# 06_-_External_ADC.net
KiCad netlist of a schematic drawn in Altium Designer
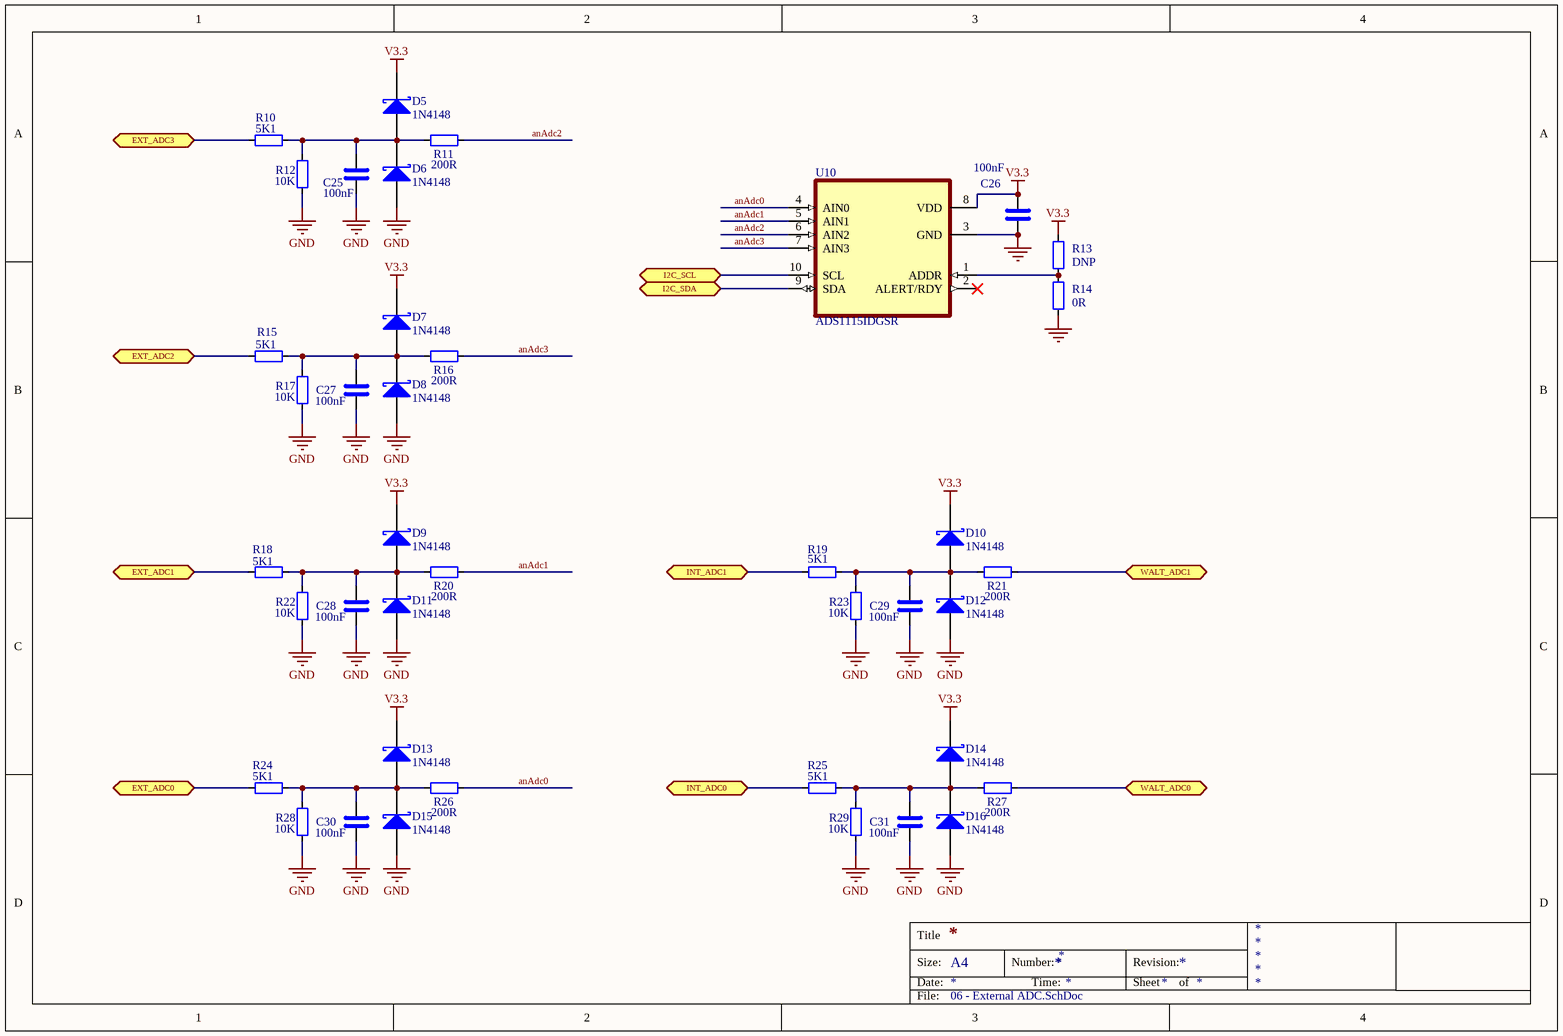
[diagram p0: 06 - External ADC.SchDoc]

(export (version "E")
  (design (tool "Eeschema 10.0.6"))
  (components
    (comp (ref "C25")
      (value "100nF")
      (footprint "CAP_0603")
      (fields (field (name "LCSC PART") "C6119867"))
      (libsource (lib "WalterFeels") (part "C"))
    )
    (comp (ref "C26")
      (value "100nF")
      (footprint "CAP_0603")
      (fields (field (name "LCSC PART") "C6119867"))
      (libsource (lib "WalterFeels") (part "C"))
    )
    (comp (ref "C27")
      (value "100nF")
      (footprint "CAP_0603")
      (fields (field (name "LCSC PART") "C6119867"))
      (libsource (lib "WalterFeels") (part "C"))
    )
    (comp (ref "C28")
      (value "100nF")
      (footprint "CAP_0603")
      (fields (field (name "LCSC PART") "C6119867"))
      (libsource (lib "WalterFeels") (part "C"))
    )
    (comp (ref "C29")
      (value "100nF")
      (footprint "CAP_0603")
      (fields (field (name "LCSC PART") "C6119867"))
      (libsource (lib "WalterFeels") (part "C"))
    )
    (comp (ref "C30")
      (value "100nF")
      (footprint "CAP_0603")
      (fields (field (name "LCSC PART") "C6119867"))
      (libsource (lib "WalterFeels") (part "C"))
    )
    (comp (ref "C31")
      (value "100nF")
      (footprint "CAP_0603")
      (fields (field (name "LCSC PART") "C6119867"))
      (libsource (lib "WalterFeels") (part "C"))
    )
    (comp (ref "D5")
      (value "1N4148")
      (footprint "SOD323_STM_NW")
      (description "1N4148_KA")
      (fields (field (name "LCSC PART") "C84063"))
      (libsource (lib "ahmet") (part "1N4148_KA"))
    )
    (comp (ref "D6")
      (value "1N4148")
      (footprint "SOD323_STM_NW")
      (description "1N4148_KA")
      (fields (field (name "LCSC PART") "C84063"))
      (libsource (lib "ahmet") (part "1N4148_KA"))
    )
    (comp (ref "D7")
      (value "1N4148")
      (footprint "SOD323_STM_NW")
      (description "1N4148_KA")
      (fields (field (name "LCSC PART") "C84063"))
      (libsource (lib "ahmet") (part "1N4148_KA"))
    )
    (comp (ref "D8")
      (value "1N4148")
      (footprint "SOD323_STM_NW")
      (description "1N4148_KA")
      (fields (field (name "LCSC PART") "C84063"))
      (libsource (lib "ahmet") (part "1N4148_KA"))
    )
    (comp (ref "D9")
      (value "1N4148")
      (footprint "SOD323_STM_NW")
      (description "1N4148_KA")
      (fields (field (name "LCSC PART") "C84063"))
      (libsource (lib "ahmet") (part "1N4148_KA"))
    )
    (comp (ref "D10")
      (value "1N4148")
      (footprint "SOD323_STM_NW")
      (description "1N4148_KA")
      (fields (field (name "LCSC PART") "C84063"))
      (libsource (lib "ahmet") (part "1N4148_KA"))
    )
    (comp (ref "D11")
      (value "1N4148")
      (footprint "SOD323_STM_NW")
      (description "1N4148_KA")
      (fields (field (name "LCSC PART") "C84063"))
      (libsource (lib "ahmet") (part "1N4148_KA"))
    )
    (comp (ref "D12")
      (value "1N4148")
      (footprint "SOD323_STM_NW")
      (description "1N4148_KA")
      (fields (field (name "LCSC PART") "C84063"))
      (libsource (lib "ahmet") (part "1N4148_KA"))
    )
    (comp (ref "D13")
      (value "1N4148")
      (footprint "SOD323_STM_NW")
      (description "1N4148_KA")
      (fields (field (name "LCSC PART") "C84063"))
      (libsource (lib "ahmet") (part "1N4148_KA"))
    )
    (comp (ref "D14")
      (value "1N4148")
      (footprint "SOD323_STM_NW")
      (description "1N4148_KA")
      (fields (field (name "LCSC PART") "C84063"))
      (libsource (lib "ahmet") (part "1N4148_KA"))
    )
    (comp (ref "D15")
      (value "1N4148")
      (footprint "SOD323_STM_NW")
      (description "1N4148_KA")
      (fields (field (name "LCSC PART") "C84063"))
      (libsource (lib "ahmet") (part "1N4148_KA"))
    )
    (comp (ref "D16")
      (value "1N4148")
      (footprint "SOD323_STM_NW")
      (description "1N4148_KA")
      (fields (field (name "LCSC PART") "C84063"))
      (libsource (lib "ahmet") (part "1N4148_KA"))
    )
    (comp (ref "R10")
      (value "5K1")
      (footprint "RES_0603")
      (fields (field (name "LCSC PART") "C23186") (field (name "Comment") "5K1 1%"))
      (libsource (lib "Device") (part "R"))
    )
    (comp (ref "R11")
      (value "200R")
      (footprint "RES_0603")
      (fields (field (name "LCSC PART") "C2907123") (field (name "Comment") "200R %5"))
      (libsource (lib "Device") (part "R"))
    )
    (comp (ref "R12")
      (value "10K")
      (footprint "RES_0603")
      (fields (field (name "LCSC PART") "C25804") (field (name "Comment") "10K 1%"))
      (libsource (lib "") (part "R_1"))
    )
    (comp (ref "R13") (value "DNP") (footprint "RES_0603") (libsource (lib "") (part "R_2")))
    (comp (ref "R14")
      (value "0R")
      (footprint "RES_0603")
      (fields (field (name "LCSC PART") "C15402"))
      (libsource (lib "") (part "R_2"))
    )
    (comp (ref "R15")
      (value "5K1")
      (footprint "RES_0603")
      (fields (field (name "LCSC PART") "C23186") (field (name "Comment") "5K1 1%"))
      (libsource (lib "Device") (part "R"))
    )
    (comp (ref "R16")
      (value "200R")
      (footprint "RES_0603")
      (fields (field (name "LCSC PART") "C2907123") (field (name "Comment") "200R %5"))
      (libsource (lib "Device") (part "R"))
    )
    (comp (ref "R17")
      (value "10K")
      (footprint "RES_0603")
      (fields (field (name "LCSC PART") "C25804") (field (name "Comment") "10K 1%"))
      (libsource (lib "") (part "R_1"))
    )
    (comp (ref "R18")
      (value "5K1")
      (footprint "RES_0603")
      (fields (field (name "LCSC PART") "C23186") (field (name "Comment") "5K1 1%"))
      (libsource (lib "Device") (part "R"))
    )
    (comp (ref "R19")
      (value "5K1")
      (footprint "RES_0603")
      (fields (field (name "LCSC PART") "C23186") (field (name "Comment") "5K1 1%"))
      (libsource (lib "Device") (part "R"))
    )
    (comp (ref "R20")
      (value "200R")
      (footprint "RES_0603")
      (fields (field (name "LCSC PART") "C2907123") (field (name "Comment") "200R %5"))
      (libsource (lib "Device") (part "R"))
    )
    (comp (ref "R21")
      (value "200R")
      (footprint "RES_0603")
      (fields (field (name "LCSC PART") "C2907123") (field (name "Comment") "200R %5"))
      (libsource (lib "Device") (part "R"))
    )
    (comp (ref "R22")
      (value "10K")
      (footprint "RES_0603")
      (fields (field (name "LCSC PART") "C25804") (field (name "Comment") "10K 1%"))
      (libsource (lib "") (part "R_1"))
    )
    (comp (ref "R23")
      (value "10K")
      (footprint "RES_0603")
      (fields (field (name "LCSC PART") "C25804") (field (name "Comment") "10K 1%"))
      (libsource (lib "") (part "R_1"))
    )
    (comp (ref "R24")
      (value "5K1")
      (footprint "RES_0603")
      (fields (field (name "LCSC PART") "C23186") (field (name "Comment") "5K1 1%"))
      (libsource (lib "Device") (part "R"))
    )
    (comp (ref "R25")
      (value "5K1")
      (footprint "RES_0603")
      (fields (field (name "LCSC PART") "C23186") (field (name "Comment") "5K1 1%"))
      (libsource (lib "Device") (part "R"))
    )
    (comp (ref "R26")
      (value "200R")
      (footprint "RES_0603")
      (fields (field (name "LCSC PART") "C2907123") (field (name "Comment") "200R %5"))
      (libsource (lib "Device") (part "R"))
    )
    (comp (ref "R27")
      (value "200R")
      (footprint "RES_0603")
      (fields (field (name "LCSC PART") "C2907123") (field (name "Comment") "200R %5"))
      (libsource (lib "Device") (part "R"))
    )
    (comp (ref "R28")
      (value "10K")
      (footprint "RES_0603")
      (fields (field (name "LCSC PART") "C25804") (field (name "Comment") "10K 1%"))
      (libsource (lib "") (part "R_1"))
    )
    (comp (ref "R29")
      (value "10K")
      (footprint "RES_0603")
      (fields (field (name "LCSC PART") "C25804") (field (name "Comment") "10K 1%"))
      (libsource (lib "") (part "R_1"))
    )
    (comp (ref "U10")
      (value "ADS1115IDGSR")
      (footprint "SOP50P490X110-10N")
      (fields (field (name "LCSC PART") "C37593"))
      (libsource (lib "ahmet") (part "ADS1015IDGSR"))
    )
  )
  (nets
    (net (code "1") (name "/EXT_ADC0") (class "Default")
      (node (ref "R24") (pin "1") (pinfunction "1_1") (pintype "passive"))
    )
    (net (code "2") (name "/EXT_ADC1") (class "Default")
      (node (ref "R18") (pin "1") (pinfunction "1_1") (pintype "passive"))
    )
    (net (code "3") (name "/EXT_ADC2") (class "Default")
      (node (ref "R15") (pin "1") (pinfunction "1_1") (pintype "passive"))
    )
    (net (code "4") (name "/EXT_ADC3") (class "Default")
      (node (ref "R10") (pin "1") (pinfunction "1_1") (pintype "passive"))
    )
    (net (code "5") (name "/I2C_SCL") (class "Default")
      (node (ref "U10") (pin "10") (pinfunction "SCL_10") (pintype "input"))
    )
    (net (code "6") (name "/I2C_SDA") (class "Default")
      (node (ref "U10") (pin "9") (pinfunction "SDA_9") (pintype "bidirectional"))
    )
    (net (code "7") (name "/INT_ADC0") (class "Default")
      (node (ref "R25") (pin "1") (pinfunction "1_1") (pintype "passive"))
    )
    (net (code "8") (name "/INT_ADC1") (class "Default")
      (node (ref "R19") (pin "1") (pinfunction "1_1") (pintype "passive"))
    )
    (net (code "9") (name "/WALT_ADC0") (class "Default")
      (node (ref "R27") (pin "2") (pinfunction "2_2") (pintype "passive"))
    )
    (net (code "10") (name "/WALT_ADC1") (class "Default")
      (node (ref "R21") (pin "2") (pinfunction "2_2") (pintype "passive"))
    )
    (net (code "11") (name "/anAdc0") (class "Default")
      (node (ref "R26") (pin "2") (pinfunction "2_2") (pintype "passive"))
      (node (ref "U10") (pin "4") (pinfunction "AIN0_4") (pintype "input"))
    )
    (net (code "12") (name "/anAdc1") (class "Default")
      (node (ref "R20") (pin "2") (pinfunction "2_2") (pintype "passive"))
      (node (ref "U10") (pin "5") (pinfunction "AIN1_5") (pintype "input"))
    )
    (net (code "13") (name "/anAdc2") (class "Default")
      (node (ref "R11") (pin "2") (pinfunction "2_2") (pintype "passive"))
      (node (ref "U10") (pin "6") (pinfunction "AIN2_6") (pintype "input"))
    )
    (net (code "14") (name "/anAdc3") (class "Default")
      (node (ref "R16") (pin "2") (pinfunction "2_2") (pintype "passive"))
      (node (ref "U10") (pin "7") (pinfunction "AIN3_7") (pintype "input"))
    )
    (net (code "15") (name "GND") (class "Default")
      (node (ref "C25") (pin "2") (pinfunction "2_2") (pintype "passive"))
      (node (ref "C26") (pin "2") (pinfunction "2_2") (pintype "passive"))
      (node (ref "C27") (pin "2") (pinfunction "2_2") (pintype "passive"))
      (node (ref "C28") (pin "2") (pinfunction "2_2") (pintype "passive"))
      (node (ref "C29") (pin "2") (pinfunction "2_2") (pintype "passive"))
      (node (ref "C30") (pin "2") (pinfunction "2_2") (pintype "passive"))
      (node (ref "C31") (pin "2") (pinfunction "2_2") (pintype "passive"))
      (node (ref "D11") (pin "2") (pinfunction "A_2") (pintype "passive"))
      (node (ref "D12") (pin "2") (pinfunction "A_2") (pintype "passive"))
      (node (ref "D15") (pin "2") (pinfunction "A_2") (pintype "passive"))
      (node (ref "D16") (pin "2") (pinfunction "A_2") (pintype "passive"))
      (node (ref "D6") (pin "2") (pinfunction "A_2") (pintype "passive"))
      (node (ref "D8") (pin "2") (pinfunction "A_2") (pintype "passive"))
      (node (ref "R12") (pin "1") (pinfunction "1_1") (pintype "passive"))
      (node (ref "R14") (pin "2") (pinfunction "2_2") (pintype "passive"))
      (node (ref "R17") (pin "1") (pinfunction "1_1") (pintype "passive"))
      (node (ref "R22") (pin "1") (pinfunction "1_1") (pintype "passive"))
      (node (ref "R23") (pin "1") (pinfunction "1_1") (pintype "passive"))
      (node (ref "R28") (pin "1") (pinfunction "1_1") (pintype "passive"))
      (node (ref "R29") (pin "1") (pinfunction "1_1") (pintype "passive"))
      (node (ref "U10") (pin "3") (pinfunction "GND_3") (pintype "power_in"))
    )
    (net (code "16") (name "Net-(D5-A)") (class "Default")
      (node (ref "C25") (pin "1") (pinfunction "1_1") (pintype "passive"))
      (node (ref "D5") (pin "2") (pinfunction "A_2") (pintype "passive"))
      (node (ref "D6") (pin "1") (pinfunction "K_1") (pintype "passive"))
      (node (ref "R10") (pin "2") (pinfunction "2_2") (pintype "passive"))
      (node (ref "R11") (pin "1") (pinfunction "1_1") (pintype "passive"))
      (node (ref "R12") (pin "2") (pinfunction "2_2") (pintype "passive"))
    )
    (net (code "17") (name "Net-(D7-A)") (class "Default")
      (node (ref "C27") (pin "1") (pinfunction "1_1") (pintype "passive"))
      (node (ref "D7") (pin "2") (pinfunction "A_2") (pintype "passive"))
      (node (ref "D8") (pin "1") (pinfunction "K_1") (pintype "passive"))
      (node (ref "R15") (pin "2") (pinfunction "2_2") (pintype "passive"))
      (node (ref "R16") (pin "1") (pinfunction "1_1") (pintype "passive"))
      (node (ref "R17") (pin "2") (pinfunction "2_2") (pintype "passive"))
    )
    (net (code "18") (name "Net-(D10-A)") (class "Default")
      (node (ref "C29") (pin "1") (pinfunction "1_1") (pintype "passive"))
      (node (ref "D10") (pin "2") (pinfunction "A_2") (pintype "passive"))
      (node (ref "D12") (pin "1") (pinfunction "K_1") (pintype "passive"))
      (node (ref "R19") (pin "2") (pinfunction "2_2") (pintype "passive"))
      (node (ref "R21") (pin "1") (pinfunction "1_1") (pintype "passive"))
      (node (ref "R23") (pin "2") (pinfunction "2_2") (pintype "passive"))
    )
    (net (code "19") (name "Net-(D11-K)") (class "Default")
      (node (ref "C28") (pin "1") (pinfunction "1_1") (pintype "passive"))
      (node (ref "D11") (pin "1") (pinfunction "K_1") (pintype "passive"))
      (node (ref "D9") (pin "2") (pinfunction "A_2") (pintype "passive"))
      (node (ref "R18") (pin "2") (pinfunction "2_2") (pintype "passive"))
      (node (ref "R20") (pin "1") (pinfunction "1_1") (pintype "passive"))
      (node (ref "R22") (pin "2") (pinfunction "2_2") (pintype "passive"))
    )
    (net (code "20") (name "Net-(D13-A)") (class "Default")
      (node (ref "C30") (pin "1") (pinfunction "1_1") (pintype "passive"))
      (node (ref "D13") (pin "2") (pinfunction "A_2") (pintype "passive"))
      (node (ref "D15") (pin "1") (pinfunction "K_1") (pintype "passive"))
      (node (ref "R24") (pin "2") (pinfunction "2_2") (pintype "passive"))
      (node (ref "R26") (pin "1") (pinfunction "1_1") (pintype "passive"))
      (node (ref "R28") (pin "2") (pinfunction "2_2") (pintype "passive"))
    )
    (net (code "21") (name "Net-(D14-A)") (class "Default")
      (node (ref "C31") (pin "1") (pinfunction "1_1") (pintype "passive"))
      (node (ref "D14") (pin "2") (pinfunction "A_2") (pintype "passive"))
      (node (ref "D16") (pin "1") (pinfunction "K_1") (pintype "passive"))
      (node (ref "R25") (pin "2") (pinfunction "2_2") (pintype "passive"))
      (node (ref "R27") (pin "1") (pinfunction "1_1") (pintype "passive"))
      (node (ref "R29") (pin "2") (pinfunction "2_2") (pintype "passive"))
    )
    (net (code "22") (name "Net-(U10-ADDR)") (class "Default")
      (node (ref "R13") (pin "2") (pinfunction "2_2") (pintype "passive"))
      (node (ref "R14") (pin "1") (pinfunction "1_1") (pintype "passive"))
      (node (ref "U10") (pin "1") (pinfunction "ADDR_1") (pintype "input"))
    )
    (net (code "23") (name "V3.3") (class "Default")
      (node (ref "C26") (pin "1") (pinfunction "1_1") (pintype "passive"))
      (node (ref "D10") (pin "1") (pinfunction "K_1") (pintype "passive"))
      (node (ref "D13") (pin "1") (pinfunction "K_1") (pintype "passive"))
      (node (ref "D14") (pin "1") (pinfunction "K_1") (pintype "passive"))
      (node (ref "D5") (pin "1") (pinfunction "K_1") (pintype "passive"))
      (node (ref "D7") (pin "1") (pinfunction "K_1") (pintype "passive"))
      (node (ref "D9") (pin "1") (pinfunction "K_1") (pintype "passive"))
      (node (ref "R13") (pin "1") (pinfunction "1_1") (pintype "passive"))
      (node (ref "U10") (pin "8") (pinfunction "VDD_8") (pintype "power_in"))
    )
    (net (code "24") (name "unconnected-(U10-ALERT{slash}RDY-Pad2)") (class "Default")
      (node (ref "U10") (pin "2") (pinfunction "ALERT/RDY_2") (pintype "output+no_connect"))
    )
  )
)
